# kawaiino_v1.net
KiCad netlist of a schematic drawn in EAGLE
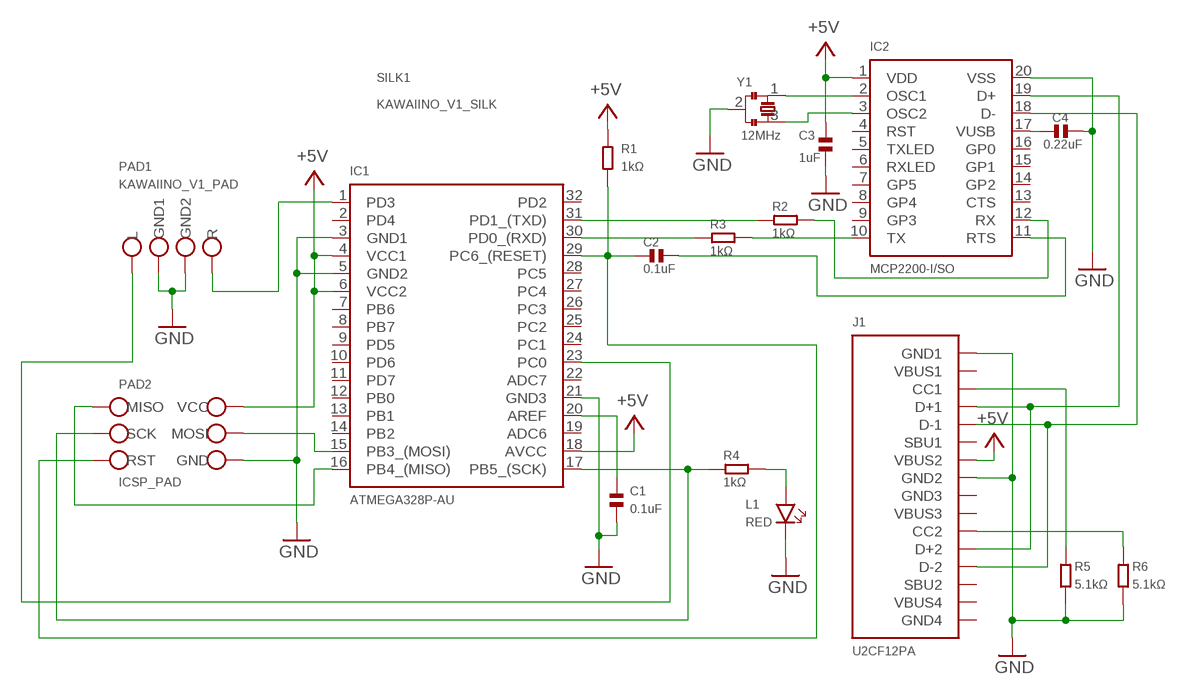
[diagram p0: schematic, sheet 1]

(export (version "E")
  (design (tool "Eeschema 10.0.6"))
  (components
    (comp (ref "C1")
      (value "0.1uF")
      (footprint "eagle-import:1608_FOOTPRINT")
      (libsource (lib "eagle-import") (part "CAPACITOR-1608"))
    )
    (comp (ref "C2")
      (value "0.1uF")
      (footprint "eagle-import:1608_FOOTPRINT")
      (libsource (lib "eagle-import") (part "CAPACITOR-1608"))
    )
    (comp (ref "C3")
      (value "1uF")
      (footprint "eagle-import:1608_FOOTPRINT")
      (libsource (lib "eagle-import") (part "CAPACITOR-1608"))
    )
    (comp (ref "C4")
      (value "0.22uF")
      (footprint "eagle-import:1608_FOOTPRINT")
      (libsource (lib "eagle-import") (part "CAPACITOR-1608"))
    )
    (comp (ref "IC1")
      (value "ATMEGA328P-AU")
      (footprint "eagle-import:TQFP-32")
      (libsource (lib "eagle-import") (part "ATMEGA328P-AU"))
    )
    (comp (ref "IC2")
      (value "MCP2200-I/SO")
      (footprint "eagle-import:SOIC20")
      (libsource (lib "eagle-import") (part "MCP2200-I/SO"))
    )
    (comp (ref "J1")
      (value "U2CF12PA")
      (footprint "eagle-import:U2CF12PA_FOOTPRINT")
      (libsource (lib "eagle-import") (part "U2CF12PA"))
    )
    (comp (ref "L1")
      (value "RED")
      (footprint "eagle-import:1608_FOOTPRINT")
      (libsource (lib "eagle-import") (part "LED-1608"))
    )
    (comp (ref "PAD1")
      (value "KAWAIINO_V1_PAD")
      (footprint "eagle-import:KAWAIINO_V1_PAD")
      (libsource (lib "eagle-import") (part "KAWAIINO_V1_PAD"))
    )
    (comp (ref "PAD2")
      (value "ICSP_PAD")
      (footprint "eagle-import:ICSP_PAD")
      (libsource (lib "eagle-import") (part "ICSP_PAD"))
    )
    (comp (ref "R1")
      (value "1kΩ")
      (footprint "eagle-import:2012_FOOTPRINT")
      (libsource (lib "eagle-import") (part "REGISTER-2012"))
    )
    (comp (ref "R2")
      (value "1kΩ")
      (footprint "eagle-import:2012_FOOTPRINT")
      (libsource (lib "eagle-import") (part "REGISTER-2012"))
    )
    (comp (ref "R3")
      (value "1kΩ")
      (footprint "eagle-import:2012_FOOTPRINT")
      (libsource (lib "eagle-import") (part "REGISTER-2012"))
    )
    (comp (ref "R4")
      (value "1kΩ")
      (footprint "eagle-import:2012_FOOTPRINT")
      (libsource (lib "eagle-import") (part "REGISTER-2012"))
    )
    (comp (ref "R5")
      (value "5.1kΩ")
      (footprint "eagle-import:2012_FOOTPRINT")
      (libsource (lib "eagle-import") (part "REGISTER-2012"))
    )
    (comp (ref "R6")
      (value "5.1kΩ")
      (footprint "eagle-import:2012_FOOTPRINT")
      (libsource (lib "eagle-import") (part "REGISTER-2012"))
    )
    (comp (ref "SILK1")
      (value "KAWAIINO_V1_SILK")
      (footprint "eagle-import:KAWAIINO_V1_SILK")
      (libsource (lib "eagle-import") (part "KAWAIINO_V1_SILK"))
    )
    (comp (ref "Y1")
      (value "12MHz")
      (footprint "eagle-import:CSTNE_G_FOOTPRINT")
      (libsource (lib "eagle-import") (part "CSTNE_G"))
    )
  )
  (nets
    (net (code "1") (name "+5V") (class "Default")
      (node (ref "C3") (pin "1") (pinfunction "P$1_1") (pintype "bidirectional"))
      (node (ref "IC1") (pin "18") (pinfunction "AVCC_18") (pintype "bidirectional"))
      (node (ref "IC1") (pin "4") (pinfunction "VCC1_4") (pintype "bidirectional"))
      (node (ref "IC1") (pin "6") (pinfunction "VCC2_6") (pintype "bidirectional"))
      (node (ref "IC2") (pin "1") (pinfunction "VDD_1") (pintype "bidirectional"))
      (node (ref "J1") (pin "7") (pinfunction "VBUS2_7") (pintype "bidirectional"))
      (node (ref "PAD2") (pin "2") (pinfunction "VCC_2") (pintype "bidirectional"))
      (node (ref "R1") (pin "1") (pinfunction "P$1_1") (pintype "bidirectional"))
    )
    (net (code "2") (name "GND") (class "Default")
      (node (ref "C1") (pin "2") (pinfunction "P$2_2") (pintype "bidirectional"))
      (node (ref "C3") (pin "2") (pinfunction "P$2_2") (pintype "bidirectional"))
      (node (ref "C4") (pin "2") (pinfunction "P$2_2") (pintype "bidirectional"))
      (node (ref "IC1") (pin "21") (pinfunction "GND3_21") (pintype "bidirectional"))
      (node (ref "IC1") (pin "3") (pinfunction "GND1_3") (pintype "bidirectional"))
      (node (ref "IC1") (pin "5") (pinfunction "GND2_5") (pintype "bidirectional"))
      (node (ref "IC2") (pin "20") (pinfunction "VSS_20") (pintype "bidirectional"))
      (node (ref "J1") (pin "1") (pinfunction "GND1_1") (pintype "bidirectional"))
      (node (ref "J1") (pin "8") (pinfunction "GND2_8") (pintype "bidirectional"))
      (node (ref "L1") (pin "2") (pinfunction "-_2") (pintype "bidirectional"))
      (node (ref "PAD1") (pin "P$2") (pinfunction "GND1_P$2") (pintype "bidirectional"))
      (node (ref "PAD1") (pin "P$3") (pinfunction "GND2_P$3") (pintype "bidirectional"))
      (node (ref "PAD2") (pin "6") (pinfunction "GND_6") (pintype "bidirectional"))
      (node (ref "R5") (pin "2") (pinfunction "P$2_2") (pintype "bidirectional"))
      (node (ref "R6") (pin "2") (pinfunction "P$2_2") (pintype "bidirectional"))
      (node (ref "Y1") (pin "2") (pinfunction "P$2_2") (pintype "bidirectional"))
    )
    (net (code "3") (name "Net-(C1-P$1)") (class "Default")
      (node (ref "C1") (pin "1") (pinfunction "P$1_1") (pintype "bidirectional"))
      (node (ref "IC1") (pin "20") (pinfunction "AREF_20") (pintype "bidirectional"))
    )
    (net (code "4") (name "Net-(C2-P$1)") (class "Default")
      (node (ref "C2") (pin "1") (pinfunction "P$1_1") (pintype "bidirectional"))
      (node (ref "IC1") (pin "29") (pinfunction "PC6_(RESET)_29") (pintype "bidirectional"))
      (node (ref "PAD2") (pin "5") (pinfunction "RST_5") (pintype "bidirectional"))
      (node (ref "R1") (pin "2") (pinfunction "P$2_2") (pintype "bidirectional"))
    )
    (net (code "5") (name "Net-(C2-P$2)") (class "Default")
      (node (ref "C2") (pin "2") (pinfunction "P$2_2") (pintype "bidirectional"))
      (node (ref "IC2") (pin "11") (pinfunction "RTS_11") (pintype "bidirectional"))
    )
    (net (code "6") (name "Net-(C4-P$1)") (class "Default")
      (node (ref "C4") (pin "1") (pinfunction "P$1_1") (pintype "bidirectional"))
      (node (ref "IC2") (pin "17") (pinfunction "VUSB_17") (pintype "bidirectional"))
    )
    (net (code "7") (name "Net-(IC1-PB3_(MOSI))") (class "Default")
      (node (ref "IC1") (pin "15") (pinfunction "PB3_(MOSI)_15") (pintype "bidirectional"))
      (node (ref "PAD2") (pin "4") (pinfunction "MOSI_4") (pintype "bidirectional"))
    )
    (net (code "8") (name "Net-(IC1-PB4_(MISO))") (class "Default")
      (node (ref "IC1") (pin "16") (pinfunction "PB4_(MISO)_16") (pintype "bidirectional"))
      (node (ref "PAD2") (pin "1") (pinfunction "MISO_1") (pintype "bidirectional"))
    )
    (net (code "9") (name "Net-(IC1-PB5_(SCK))") (class "Default")
      (node (ref "IC1") (pin "17") (pinfunction "PB5_(SCK)_17") (pintype "bidirectional"))
      (node (ref "PAD2") (pin "3") (pinfunction "SCK_3") (pintype "bidirectional"))
      (node (ref "R4") (pin "1") (pinfunction "P$1_1") (pintype "bidirectional"))
    )
    (net (code "10") (name "Net-(IC1-PC0)") (class "Default")
      (node (ref "IC1") (pin "23") (pinfunction "PC0_23") (pintype "bidirectional"))
      (node (ref "PAD1") (pin "P$1") (pinfunction "L_P$1") (pintype "bidirectional"))
    )
    (net (code "11") (name "Net-(IC1-PD0_(RXD))") (class "Default")
      (node (ref "IC1") (pin "30") (pinfunction "PD0_(RXD)_30") (pintype "bidirectional"))
      (node (ref "R3") (pin "1") (pinfunction "P$1_1") (pintype "bidirectional"))
    )
    (net (code "12") (name "Net-(IC1-PD1_(TXD))") (class "Default")
      (node (ref "IC1") (pin "31") (pinfunction "PD1_(TXD)_31") (pintype "bidirectional"))
      (node (ref "R2") (pin "1") (pinfunction "P$1_1") (pintype "bidirectional"))
    )
    (net (code "13") (name "Net-(IC1-PD3)") (class "Default")
      (node (ref "IC1") (pin "1") (pinfunction "PD3_1") (pintype "bidirectional"))
      (node (ref "PAD1") (pin "P$4") (pinfunction "R_P$4") (pintype "bidirectional"))
    )
    (net (code "14") (name "Net-(IC2-D+)") (class "Default")
      (node (ref "IC2") (pin "19") (pinfunction "D+_19") (pintype "bidirectional"))
      (node (ref "J1") (pin "12") (pinfunction "D+2_12") (pintype "bidirectional"))
      (node (ref "J1") (pin "4") (pinfunction "D+1_4") (pintype "bidirectional"))
    )
    (net (code "15") (name "Net-(IC2-D-)") (class "Default")
      (node (ref "IC2") (pin "18") (pinfunction "D-_18") (pintype "bidirectional"))
      (node (ref "J1") (pin "13") (pinfunction "D-2_13") (pintype "bidirectional"))
      (node (ref "J1") (pin "5") (pinfunction "D-1_5") (pintype "bidirectional"))
    )
    (net (code "16") (name "Net-(IC2-OSC1)") (class "Default")
      (node (ref "IC2") (pin "2") (pinfunction "OSC1_2") (pintype "bidirectional"))
      (node (ref "Y1") (pin "1") (pinfunction "P$1_1") (pintype "bidirectional"))
    )
    (net (code "17") (name "Net-(IC2-OSC2)") (class "Default")
      (node (ref "IC2") (pin "3") (pinfunction "OSC2_3") (pintype "bidirectional"))
      (node (ref "Y1") (pin "3") (pinfunction "P$3_3") (pintype "bidirectional"))
    )
    (net (code "18") (name "Net-(IC2-RX)") (class "Default")
      (node (ref "IC2") (pin "12") (pinfunction "RX_12") (pintype "bidirectional"))
      (node (ref "R2") (pin "2") (pinfunction "P$2_2") (pintype "bidirectional"))
    )
    (net (code "19") (name "Net-(IC2-TX)") (class "Default")
      (node (ref "IC2") (pin "10") (pinfunction "TX_10") (pintype "bidirectional"))
      (node (ref "R3") (pin "2") (pinfunction "P$2_2") (pintype "bidirectional"))
    )
    (net (code "20") (name "Net-(J1-CC1)") (class "Default")
      (node (ref "J1") (pin "3") (pinfunction "CC1_3") (pintype "bidirectional"))
      (node (ref "R5") (pin "1") (pinfunction "P$1_1") (pintype "bidirectional"))
    )
    (net (code "21") (name "Net-(J1-CC2)") (class "Default")
      (node (ref "J1") (pin "11") (pinfunction "CC2_11") (pintype "bidirectional"))
      (node (ref "R6") (pin "1") (pinfunction "P$1_1") (pintype "bidirectional"))
    )
    (net (code "22") (name "Net-(L1-+)") (class "Default")
      (node (ref "L1") (pin "1") (pinfunction "+_1") (pintype "bidirectional"))
      (node (ref "R4") (pin "2") (pinfunction "P$2_2") (pintype "bidirectional"))
    )
    (net (code "23") (name "unconnected-(IC1-ADC6-Pad19)") (class "Default")
      (node (ref "IC1") (pin "19") (pinfunction "ADC6_19") (pintype "bidirectional"))
    )
    (net (code "24") (name "unconnected-(IC1-ADC7-Pad22)") (class "Default")
      (node (ref "IC1") (pin "22") (pinfunction "ADC7_22") (pintype "bidirectional"))
    )
    (net (code "25") (name "unconnected-(IC1-PB0-Pad12)") (class "Default")
      (node (ref "IC1") (pin "12") (pinfunction "PB0_12") (pintype "bidirectional"))
    )
    (net (code "26") (name "unconnected-(IC1-PB1-Pad13)") (class "Default")
      (node (ref "IC1") (pin "13") (pinfunction "PB1_13") (pintype "bidirectional"))
    )
    (net (code "27") (name "unconnected-(IC1-PB2-Pad14)") (class "Default")
      (node (ref "IC1") (pin "14") (pinfunction "PB2_14") (pintype "bidirectional"))
    )
    (net (code "28") (name "unconnected-(IC1-PB6-Pad7)") (class "Default")
      (node (ref "IC1") (pin "7") (pinfunction "PB6_7") (pintype "bidirectional"))
    )
    (net (code "29") (name "unconnected-(IC1-PB7-Pad8)") (class "Default")
      (node (ref "IC1") (pin "8") (pinfunction "PB7_8") (pintype "bidirectional"))
    )
    (net (code "30") (name "unconnected-(IC1-PC1-Pad24)") (class "Default")
      (node (ref "IC1") (pin "24") (pinfunction "PC1_24") (pintype "bidirectional"))
    )
    (net (code "31") (name "unconnected-(IC1-PC2-Pad25)") (class "Default")
      (node (ref "IC1") (pin "25") (pinfunction "PC2_25") (pintype "bidirectional"))
    )
    (net (code "32") (name "unconnected-(IC1-PC3-Pad26)") (class "Default")
      (node (ref "IC1") (pin "26") (pinfunction "PC3_26") (pintype "bidirectional"))
    )
    (net (code "33") (name "unconnected-(IC1-PC4-Pad27)") (class "Default")
      (node (ref "IC1") (pin "27") (pinfunction "PC4_27") (pintype "bidirectional"))
    )
    (net (code "34") (name "unconnected-(IC1-PC5-Pad28)") (class "Default")
      (node (ref "IC1") (pin "28") (pinfunction "PC5_28") (pintype "bidirectional"))
    )
    (net (code "35") (name "unconnected-(IC1-PD2-Pad32)") (class "Default")
      (node (ref "IC1") (pin "32") (pinfunction "PD2_32") (pintype "bidirectional"))
    )
    (net (code "36") (name "unconnected-(IC1-PD4-Pad2)") (class "Default")
      (node (ref "IC1") (pin "2") (pinfunction "PD4_2") (pintype "bidirectional"))
    )
    (net (code "37") (name "unconnected-(IC1-PD5-Pad9)") (class "Default")
      (node (ref "IC1") (pin "9") (pinfunction "PD5_9") (pintype "bidirectional"))
    )
    (net (code "38") (name "unconnected-(IC1-PD6-Pad10)") (class "Default")
      (node (ref "IC1") (pin "10") (pinfunction "PD6_10") (pintype "bidirectional"))
    )
    (net (code "39") (name "unconnected-(IC1-PD7-Pad11)") (class "Default")
      (node (ref "IC1") (pin "11") (pinfunction "PD7_11") (pintype "bidirectional"))
    )
    (net (code "40") (name "unconnected-(IC2-CTS-Pad13)") (class "Default")
      (node (ref "IC2") (pin "13") (pinfunction "CTS_13") (pintype "bidirectional"))
    )
    (net (code "41") (name "unconnected-(IC2-GP0-Pad16)") (class "Default")
      (node (ref "IC2") (pin "16") (pinfunction "GP0_16") (pintype "bidirectional"))
    )
    (net (code "42") (name "unconnected-(IC2-GP1-Pad15)") (class "Default")
      (node (ref "IC2") (pin "15") (pinfunction "GP1_15") (pintype "bidirectional"))
    )
    (net (code "43") (name "unconnected-(IC2-GP2-Pad14)") (class "Default")
      (node (ref "IC2") (pin "14") (pinfunction "GP2_14") (pintype "bidirectional"))
    )
    (net (code "44") (name "unconnected-(IC2-GP3-Pad9)") (class "Default")
      (node (ref "IC2") (pin "9") (pinfunction "GP3_9") (pintype "bidirectional"))
    )
    (net (code "45") (name "unconnected-(IC2-GP4-Pad8)") (class "Default")
      (node (ref "IC2") (pin "8") (pinfunction "GP4_8") (pintype "bidirectional"))
    )
    (net (code "46") (name "unconnected-(IC2-GP5-Pad7)") (class "Default")
      (node (ref "IC2") (pin "7") (pinfunction "GP5_7") (pintype "bidirectional"))
    )
    (net (code "47") (name "unconnected-(IC2-RST-Pad4)") (class "Default")
      (node (ref "IC2") (pin "4") (pinfunction "RST_4") (pintype "bidirectional"))
    )
    (net (code "48") (name "unconnected-(IC2-RXLED-Pad6)") (class "Default")
      (node (ref "IC2") (pin "6") (pinfunction "RXLED_6") (pintype "bidirectional"))
    )
    (net (code "49") (name "unconnected-(IC2-TXLED-Pad5)") (class "Default")
      (node (ref "IC2") (pin "5") (pinfunction "TXLED_5") (pintype "bidirectional"))
    )
    (net (code "50") (name "unconnected-(J1-GND3-Pad9)") (class "Default")
      (node (ref "J1") (pin "9") (pinfunction "GND3_9") (pintype "bidirectional"))
    )
    (net (code "51") (name "unconnected-(J1-GND4-Pad16)") (class "Default")
      (node (ref "J1") (pin "16") (pinfunction "GND4_16") (pintype "bidirectional"))
    )
    (net (code "52") (name "unconnected-(J1-SBU1-Pad6)") (class "Default")
      (node (ref "J1") (pin "6") (pinfunction "SBU1_6") (pintype "bidirectional"))
    )
    (net (code "53") (name "unconnected-(J1-SBU2-Pad14)") (class "Default")
      (node (ref "J1") (pin "14") (pinfunction "SBU2_14") (pintype "bidirectional"))
    )
    (net (code "54") (name "unconnected-(J1-VBUS1-Pad2)") (class "Default")
      (node (ref "J1") (pin "2") (pinfunction "VBUS1_2") (pintype "bidirectional"))
    )
    (net (code "55") (name "unconnected-(J1-VBUS3-Pad10)") (class "Default")
      (node (ref "J1") (pin "10") (pinfunction "VBUS3_10") (pintype "bidirectional"))
    )
    (net (code "56") (name "unconnected-(J1-VBUS4-Pad15)") (class "Default")
      (node (ref "J1") (pin "15") (pinfunction "VBUS4_15") (pintype "bidirectional"))
    )
  )
)
